# smoothieboard-alt-p6.net
KiCad netlist of a schematic drawn in Altium Designer
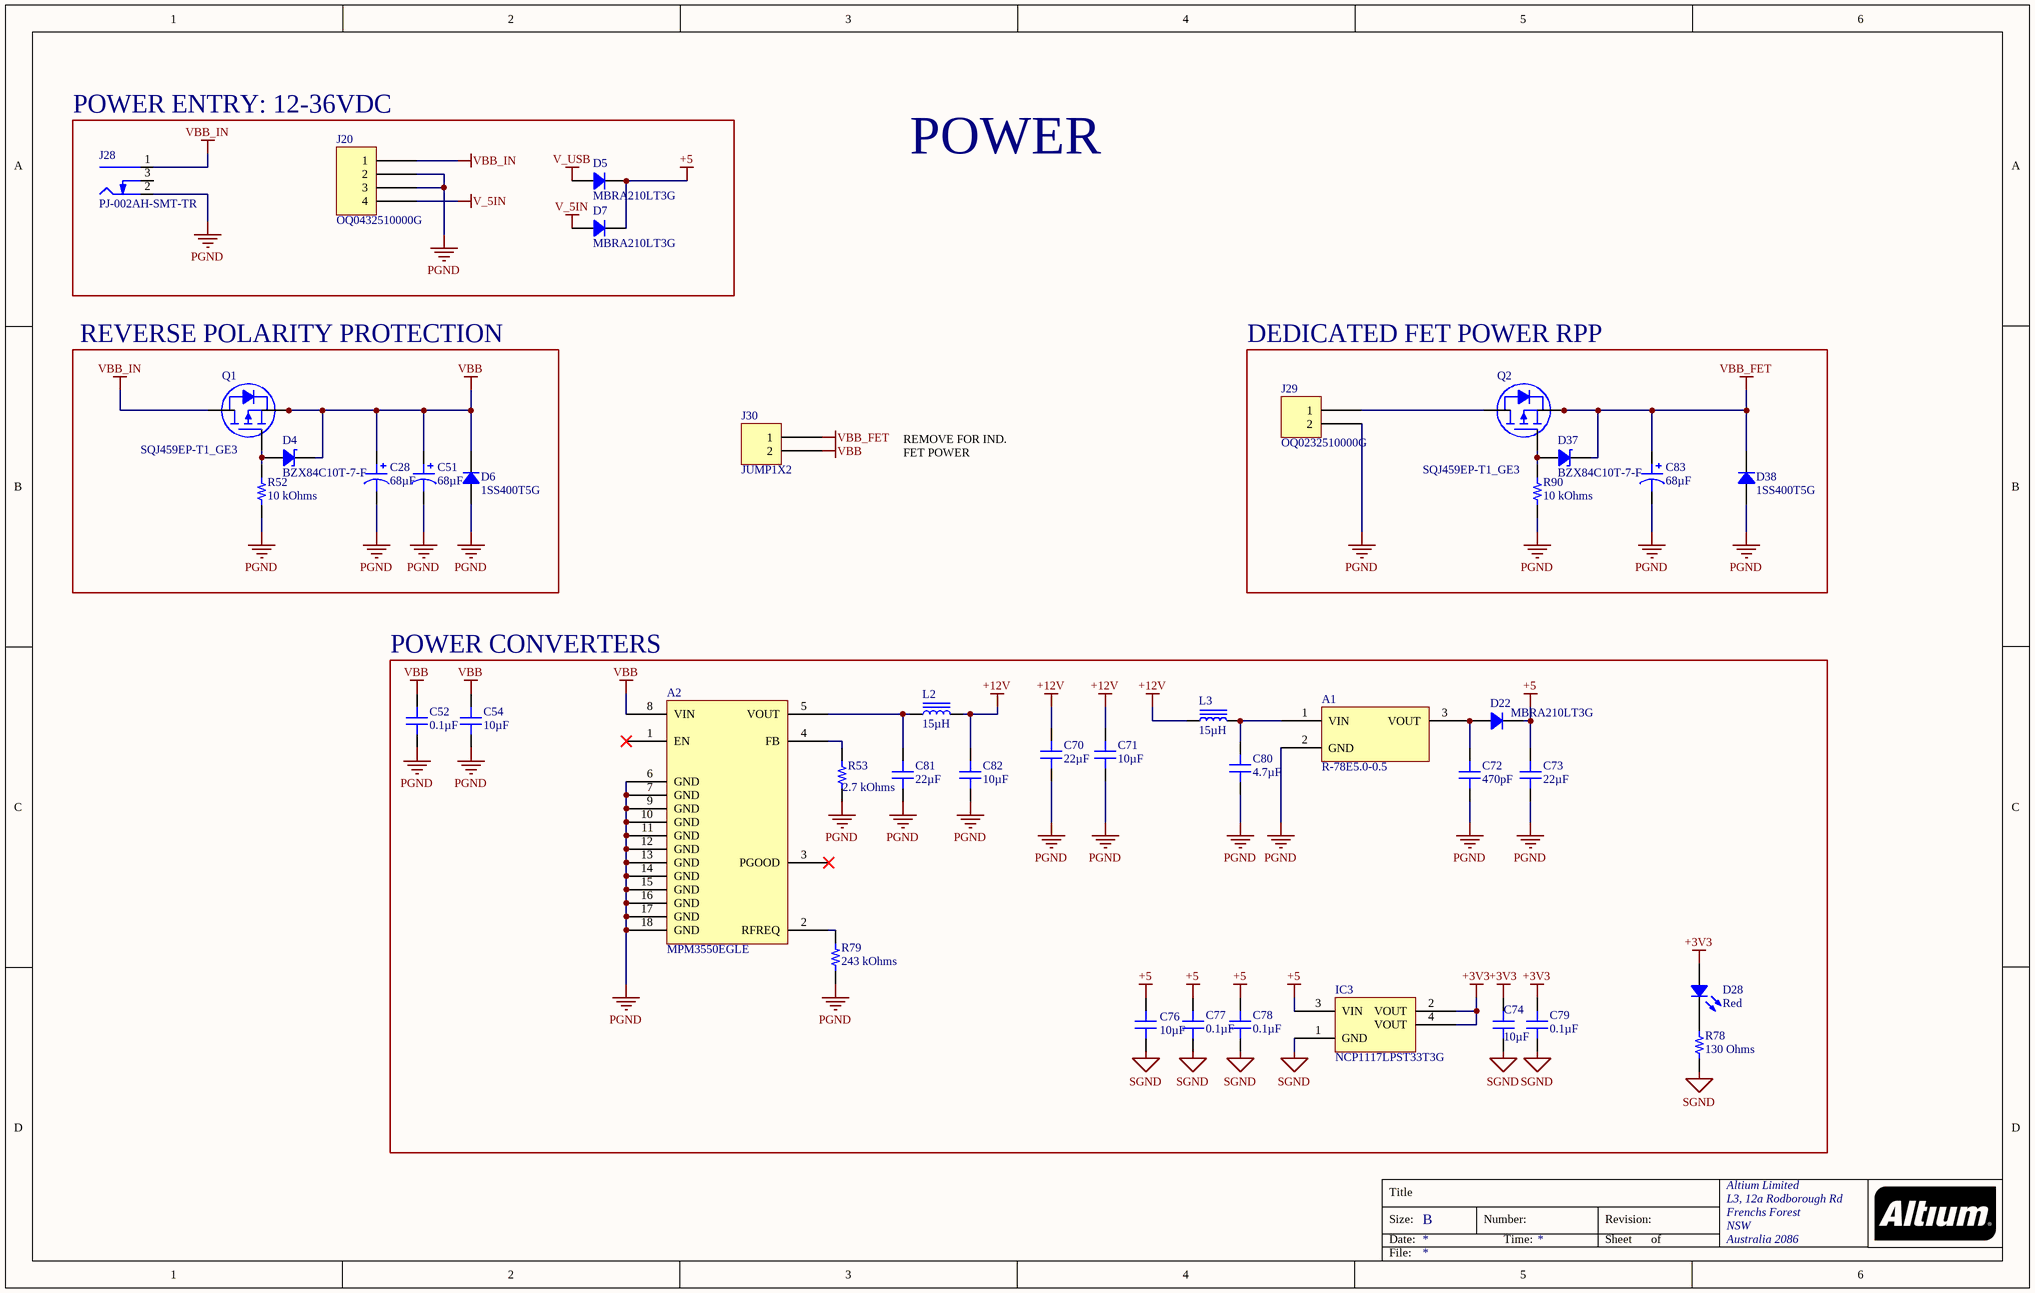
[diagram p0: smoothieboard-alt-p6.SchDoc]

(export (version "E")
  (design (tool "Eeschema 10.0.6"))
  (components
    (comp (ref "A1")
      (value "R-78E5.0-0.5")
      (footprint "RECOM POWER R-78E3.3-1.0")
      (description "DC DC CONVERTER 5V 3W")
      (fields (field (name "MANUFACTURER") "Recom Power"))
      (libsource (lib "CAL") (part "RECOM R-78E"))
    )
    (comp (ref "A2")
      (value "MPM3550EGLE")
      (footprint "MPS LGA-18 12x12x4.2mm")
      (description "DC/DC POWER MODULE 5A 1.0 TO 12.")
      (fields (field (name "MANUFACTURER") "Monolithic Power Systems Inc."))
      (libsource (lib "CAL") (part "MPS MPM3550E"))
    )
    (comp (ref "C28")
      (value "68µF")
      (footprint "CAP ALSMD 8.3MM H10.5MM")
      (description "CAP ALUM 68UF 20% 63V SMD")
      (fields
        (field (name "PART NUMBER") "EEE-FK1J680UP")
        (field (name "MANUFACTURER") "Panasonic Electronic Components")
      )
      (libsource (lib "CAL") (part "Polarised Capacitor"))
    )
    (comp (ref "C51")
      (value "68µF")
      (footprint "CAP ALSMD 8.3MM H10.5MM")
      (description "CAP ALUM 68UF 20% 63V SMD")
      (fields
        (field (name "PART NUMBER") "EEE-FK1J680UP")
        (field (name "MANUFACTURER") "Panasonic Electronic Components")
      )
      (libsource (lib "CAL") (part "Polarised Capacitor"))
    )
    (comp (ref "C52")
      (value "0.1µF")
      (footprint "CAP 0805_2012")
      (description "CAP CER 0.1UF 50V X7R 0805")
      (fields (field (name "PART NUMBER") "0805J0500104JXT") (field (name "MANUFACTURER") "Knowles Syfer"))
      (libsource (lib "CAL") (part "Capacitor"))
    )
    (comp (ref "C54")
      (value "10µF")
      (footprint "CAP 0805_2012")
      (description "0805 (2012MM) X5R (EIA) 50VDC 10")
      (fields
        (field (name "PART NUMBER") "GRM21BR61H106KE43L")
        (field (name "MANUFACTURER") "Murata Electronics")
      )
      (libsource (lib "CAL") (part "Capacitor"))
    )
    (comp (ref "C70")
      (value "22µF")
      (footprint "CAP 0805_2012")
      (description "CAP CER 22UF 16V X5R 0805")
      (fields
        (field (name "PART NUMBER") "CL21A226MOCLRNC")
        (field (name "MANUFACTURER") "Samsung Electro-Mechanics")
      )
      (libsource (lib "CAL") (part "Capacitor"))
    )
    (comp (ref "C71")
      (value "10µF")
      (footprint "CAP 0805_2012")
      (description "0805 (2012MM) X5R (EIA) 50VDC 10")
      (fields
        (field (name "PART NUMBER") "GRM21BR61H106KE43L")
        (field (name "MANUFACTURER") "Murata Electronics")
      )
      (libsource (lib "CAL") (part "Capacitor"))
    )
    (comp (ref "C72")
      (value "470pF")
      (footprint "CAP 0805_2012")
      (description "CAP CER 470PF 16V X7R 0805")
      (fields (field (name "PART NUMBER") "885012207031") (field (name "MANUFACTURER") "Würth Elektronik"))
      (libsource (lib "CAL") (part "Capacitor"))
    )
    (comp (ref "C73")
      (value "22µF")
      (footprint "CAP 0805_2012")
      (description "CAP CER 22UF 16V X5R 0805")
      (fields
        (field (name "PART NUMBER") "CL21A226MOCLRNC")
        (field (name "MANUFACTURER") "Samsung Electro-Mechanics")
      )
      (libsource (lib "CAL") (part "Capacitor"))
    )
    (comp (ref "C74")
      (value "10µF")
      (footprint "CAP 0603_1608")
      (description "CAP CER 10UF 6.3V X5R 0603")
      (fields
        (field (name "PART NUMBER") "GRM188R60J106KE47D")
        (field (name "MANUFACTURER") "Murata Electronics")
      )
      (libsource (lib "CAL") (part "Capacitor"))
    )
    (comp (ref "C76")
      (value "10µF")
      (footprint "CAP 0603_1608")
      (description "CAP CER 10UF 6.3V X5R 0603")
      (fields
        (field (name "PART NUMBER") "GRM188R60J106KE47D")
        (field (name "MANUFACTURER") "Murata Electronics")
      )
      (libsource (lib "CAL") (part "Capacitor"))
    )
    (comp (ref "C77")
      (value "0.1µF")
      (footprint "CAP 0402_1005")
      (description "CAP CER 0.1UF 6.3V X5R 0402")
      (fields (field (name "PART NUMBER") "CC0402MRX5R5BB104") (field (name "MANUFACTURER") "Yageo"))
      (libsource (lib "CAL") (part "Capacitor"))
    )
    (comp (ref "C78")
      (value "0.1µF")
      (footprint "CAP 0402_1005")
      (description "CAP CER 0.1UF 6.3V X5R 0402")
      (fields (field (name "PART NUMBER") "CC0402MRX5R5BB104") (field (name "MANUFACTURER") "Yageo"))
      (libsource (lib "CAL") (part "Capacitor"))
    )
    (comp (ref "C79")
      (value "0.1µF")
      (footprint "CAP 0402_1005")
      (description "CAP CER 0.1UF 6.3V X5R 0402")
      (fields (field (name "PART NUMBER") "CC0402MRX5R5BB104") (field (name "MANUFACTURER") "Yageo"))
      (libsource (lib "CAL") (part "Capacitor"))
    )
    (comp (ref "C80")
      (value "4.7µF")
      (footprint "CAP 0805_2012")
      (description "CAP CER 4.7UF 50V X7S 0805")
      (fields
        (field (name "PART NUMBER") "GRM21BC71H475KE11K")
        (field (name "MANUFACTURER") "Murata Electronics")
      )
      (libsource (lib "CAL") (part "Capacitor"))
    )
    (comp (ref "C81")
      (value "22µF")
      (footprint "CAP 0805_2012")
      (description "CAP CER 22UF 16V X5R 0805")
      (fields
        (field (name "PART NUMBER") "CL21A226MOCLRNC")
        (field (name "MANUFACTURER") "Samsung Electro-Mechanics")
      )
      (libsource (lib "CAL") (part "Capacitor"))
    )
    (comp (ref "C82")
      (value "10µF")
      (footprint "CAP 0805_2012")
      (description "0805 (2012MM) X5R (EIA) 50VDC 10")
      (fields
        (field (name "PART NUMBER") "GRM21BR61H106KE43L")
        (field (name "MANUFACTURER") "Murata Electronics")
      )
      (libsource (lib "CAL") (part "Capacitor"))
    )
    (comp (ref "C83")
      (value "68µF")
      (footprint "CAP ALSMD 8.3MM H10.5MM")
      (description "CAP ALUM 68UF 20% 63V SMD")
      (fields
        (field (name "PART NUMBER") "EEE-FK1J680UP")
        (field (name "MANUFACTURER") "Panasonic Electronic Components")
      )
      (libsource (lib "CAL") (part "Polarised Capacitor"))
    )
    (comp (ref "D4")
      (value "BZX84C10T-7-F")
      (footprint "DIODES SOT-523")
      (description "DIODE ZENER 10V 150MW SOT523")
      (fields (field (name "MANUFACTURER") "Diodes Incorporated") (field (name "TOLERANCE") "±6%"))
      (libsource (lib "CAL") (part "Diode Zener"))
    )
    (comp (ref "D5")
      (value "MBRA210LT3G")
      (footprint "DO214AC SMA")
      (description "DIODE SCHOTTKY 10V 2A SMA")
      (fields (field (name "MANUFACTURER") "ON Semiconductor"))
      (libsource (lib "CAL") (part "Diode"))
    )
    (comp (ref "D6")
      (value "1SS400T5G")
      (footprint "SOD-523")
      (description "DIODE GEN PURP 100V 200MA SOD523")
      (fields (field (name "MANUFACTURER") "ON Semiconductor"))
      (libsource (lib "CAL") (part "Diode"))
    )
    (comp (ref "D7")
      (value "MBRA210LT3G")
      (footprint "DO214AC SMA")
      (description "DIODE SCHOTTKY 10V 2A SMA")
      (fields (field (name "MANUFACTURER") "ON Semiconductor"))
      (libsource (lib "CAL") (part "Diode"))
    )
    (comp (ref "D22")
      (value "MBRA210LT3G")
      (footprint "DO214AC SMA")
      (description "DIODE SCHOTTKY 10V 2A SMA")
      (fields (field (name "MANUFACTURER") "ON Semiconductor"))
      (libsource (lib "CAL") (part "Diode"))
    )
    (comp (ref "D28")
      (value "Red")
      (footprint "LED 0603_1608 RED")
      (description "LED RED CLEAR 2SMD")
      (fields
        (field (name "PART NUMBER") "EAST16084RA0")
        (field (name "MANUFACTURER") "Everlight Electronics Co Ltd")
      )
      (libsource (lib "CAL") (part "LED"))
    )
    (comp (ref "D37")
      (value "BZX84C10T-7-F")
      (footprint "DIODES SOT-523")
      (description "DIODE ZENER 10V 150MW SOT523")
      (fields (field (name "MANUFACTURER") "Diodes Incorporated") (field (name "TOLERANCE") "±6%"))
      (libsource (lib "CAL") (part "Diode Zener"))
    )
    (comp (ref "D38")
      (value "1SS400T5G")
      (footprint "SOD-523")
      (description "DIODE GEN PURP 100V 200MA SOD523")
      (fields (field (name "MANUFACTURER") "ON Semiconductor"))
      (libsource (lib "CAL") (part "Diode"))
    )
    (comp (ref "IC3")
      (value "NCP1117LPST33T3G")
      (footprint "ON SEMI SOT-223 ST(318H)")
      (description "IC REG LINEAR 3.3V 1A SOT223")
      (fields (field (name "MANUFACTURER") "ON Semiconductor"))
      (libsource (lib "CAL") (part "ON Semi NCP1117"))
    )
    (comp (ref "J20")
      (value "OQ0432510000G")
      (footprint "FCI 06-381-4PIN")
      (description "TERM BLOCK HDR 4POS 90DEG 3.81MM")
      (fields (field (name "MANUFACTURER") "Amphenol Anytek"))
      (libsource (lib "CAL") (part "4 Pin"))
    )
    (comp (ref "J28")
      (value "PJ-002AH-SMT-TR")
      (footprint "CUI PJ-002AH-SMT-TR")
      (description "CONN PWR JACK 2X5.5MM SOLDER")
      (fields (field (name "MANUFACTURER") "CUI Devices"))
      (libsource (lib "CAL") (part "Barrel Connector"))
    )
    (comp (ref "J29")
      (value "OQ0232510000G")
      (footprint "FCI 06-381-2PIN")
      (description "TERM BLOCK HDR 2POS 90DEG 3.81MM")
      (fields (field (name "MANUFACTURER") "Amphenol Anytek"))
      (libsource (lib "CAL") (part "2 Pin"))
    )
    (comp (ref "J30")
      (value "JUMP1X2")
      (footprint "smoothie-lib:JUMP1X2")
      (libsource (lib "smoothie-lib") (part "JUMP1X2"))
    )
    (comp (ref "L2")
      (value "15µH")
      (footprint "IND 0806_2016")
      (description "FIXED IND 15UH 420MA 1.895OHM SM")
      (fields
        (field (name "PART NUMBER") "SDED20161T-150MS")
        (field (name "MANUFACTURER") "Delta Electronics/Cyntec")
      )
      (libsource (lib "CAL") (part "Inductor"))
    )
    (comp (ref "L3")
      (value "15µH")
      (footprint "IND 0806_2016")
      (description "FIXED IND 15UH 420MA 1.895OHM SM")
      (fields
        (field (name "PART NUMBER") "SDED20161T-150MS")
        (field (name "MANUFACTURER") "Delta Electronics/Cyntec")
      )
      (libsource (lib "CAL") (part "Inductor"))
    )
    (comp (ref "Q1")
      (value "SQJ459EP-T1_GE3")
      (footprint "POWER PAK SO-8")
      (libsource (lib "smoothie-lib") (part "SQJ459EP-T1_GE3"))
    )
    (comp (ref "Q2")
      (value "SQJ459EP-T1_GE3")
      (footprint "POWER PAK SO-8")
      (libsource (lib "smoothie-lib") (part "SQJ459EP-T1_GE3"))
    )
    (comp (ref "R52")
      (value "10 kOhms")
      (footprint "RES 0402_1005")
      (description "RES SMD 10K OHM 5% 1/16W 0402")
      (fields (field (name "PART NUMBER") "CRCW040210K0JNTD") (field (name "MANUFACTURER") "Vishay Dale"))
      (libsource (lib "CAL") (part "Resistor"))
    )
    (comp (ref "R53")
      (value "2.7 kOhms")
      (footprint "RES 0402_1005")
      (description "RES SMD 2.7K OHM 1% 1/5W 0402")
      (fields (field (name "PART NUMBER") "CRCW04022K70FKEDHP") (field (name "MANUFACTURER") "Vishay Dale"))
      (libsource (lib "CAL") (part "Resistor"))
    )
    (comp (ref "R78")
      (value "130 Ohms")
      (footprint "RES 0402_1005")
      (description "RES SMD 130 OHM 5% 1/5W 0402")
      (fields
        (field (name "PART NUMBER") "ERJ-PA2J131X")
        (field (name "MANUFACTURER") "Panasonic Electronic Components")
      )
      (libsource (lib "CAL") (part "Resistor"))
    )
    (comp (ref "R79")
      (value "243 kOhms")
      (footprint "RES 0402_1005")
      (description "RES SMD 243K OHM 1% 1/16W 0402")
      (fields (field (name "PART NUMBER") "CR0402-FX-2433GLF") (field (name "MANUFACTURER") "Bourns Inc."))
      (libsource (lib "CAL") (part "Resistor"))
    )
    (comp (ref "R90")
      (value "10 kOhms")
      (footprint "RES 0402_1005")
      (description "RES SMD 10K OHM 5% 1/16W 0402")
      (fields (field (name "PART NUMBER") "CRCW040210K0JNTD") (field (name "MANUFACTURER") "Vishay Dale"))
      (libsource (lib "CAL") (part "Resistor"))
    )
  )
  (nets
    (net (code "1") (name "+3V3") (class "Default")
      (node (ref "C74") (pin "2") (pinfunction "2_2") (pintype "passive"))
      (node (ref "C79") (pin "2") (pinfunction "2_2") (pintype "passive"))
      (node (ref "D28") (pin "1") (pinfunction "1_1") (pintype "passive"))
      (node (ref "IC3") (pin "2") (pinfunction "VOUT_2") (pintype "passive"))
      (node (ref "IC3") (pin "4") (pinfunction "VOUT_4") (pintype "passive"))
    )
    (net (code "2") (name "+5") (class "Default")
      (node (ref "C73") (pin "2") (pinfunction "2_2") (pintype "passive"))
      (node (ref "C76") (pin "2") (pinfunction "2_2") (pintype "passive"))
      (node (ref "C77") (pin "2") (pinfunction "2_2") (pintype "passive"))
      (node (ref "C78") (pin "2") (pinfunction "2_2") (pintype "passive"))
      (node (ref "D22") (pin "2") (pinfunction "2_2") (pintype "passive"))
      (node (ref "D5") (pin "2") (pinfunction "2_2") (pintype "passive"))
      (node (ref "D7") (pin "2") (pinfunction "2_2") (pintype "passive"))
      (node (ref "IC3") (pin "3") (pinfunction "VIN_3") (pintype "passive"))
    )
    (net (code "3") (name "+12V") (class "Default")
      (node (ref "C70") (pin "2") (pinfunction "2_2") (pintype "passive"))
      (node (ref "C71") (pin "2") (pinfunction "2_2") (pintype "passive"))
      (node (ref "C82") (pin "2") (pinfunction "2_2") (pintype "passive"))
      (node (ref "L2") (pin "2") (pinfunction "2_2") (pintype "passive"))
      (node (ref "L3") (pin "1") (pinfunction "1_1") (pintype "passive"))
    )
    (net (code "4") (name "Net-(A1-VIN)") (class "Default")
      (node (ref "A1") (pin "1") (pinfunction "VIN_1") (pintype "passive"))
      (node (ref "C80") (pin "2") (pinfunction "2_2") (pintype "passive"))
      (node (ref "L3") (pin "2") (pinfunction "2_2") (pintype "passive"))
    )
    (net (code "5") (name "Net-(A1-VOUT)") (class "Default")
      (node (ref "A1") (pin "3") (pinfunction "VOUT_3") (pintype "passive"))
      (node (ref "C72") (pin "2") (pinfunction "2_2") (pintype "passive"))
      (node (ref "D22") (pin "1") (pinfunction "1_1") (pintype "passive"))
    )
    (net (code "6") (name "Net-(A2-FB)") (class "Default")
      (node (ref "A2") (pin "4") (pinfunction "FB_4") (pintype "passive"))
      (node (ref "R53") (pin "2") (pinfunction "2_2") (pintype "passive"))
    )
    (net (code "7") (name "Net-(A2-RFREQ)") (class "Default")
      (node (ref "A2") (pin "2") (pinfunction "RFREQ_2") (pintype "passive"))
      (node (ref "R79") (pin "2") (pinfunction "2_2") (pintype "passive"))
    )
    (net (code "8") (name "Net-(A2-VOUT)") (class "Default")
      (node (ref "A2") (pin "5") (pinfunction "VOUT_5") (pintype "passive"))
      (node (ref "C81") (pin "2") (pinfunction "2_2") (pintype "passive"))
      (node (ref "L2") (pin "1") (pinfunction "1_1") (pintype "passive"))
    )
    (net (code "9") (name "Net-(D28-Pad2)") (class "Default")
      (node (ref "D28") (pin "2") (pinfunction "2_2") (pintype "passive"))
      (node (ref "R78") (pin "2") (pinfunction "2_2") (pintype "passive"))
    )
    (net (code "10") (name "Net-(Q1-G)") (class "Default")
      (node (ref "D4") (pin "1") (pinfunction "1_1") (pintype "passive"))
      (node (ref "Q1") (pin "4") (pinfunction "G_4") (pintype "passive"))
      (node (ref "R52") (pin "2") (pinfunction "2_2") (pintype "passive"))
    )
    (net (code "11") (name "Net-(Q2-D)") (class "Default")
      (node (ref "J29") (pin "1") (pinfunction "1_1") (pintype "passive"))
      (node (ref "Q2") (pin "5") (pinfunction "D_5") (pintype "passive"))
    )
    (net (code "12") (name "Net-(Q2-G)") (class "Default")
      (node (ref "D37") (pin "1") (pinfunction "1_1") (pintype "passive"))
      (node (ref "Q2") (pin "4") (pinfunction "G_4") (pintype "passive"))
      (node (ref "R90") (pin "2") (pinfunction "2_2") (pintype "passive"))
    )
    (net (code "13") (name "PGND") (class "Default")
      (node (ref "A1") (pin "2") (pinfunction "GND_2") (pintype "passive"))
      (node (ref "A2") (pin "10") (pinfunction "GND_10") (pintype "passive"))
      (node (ref "A2") (pin "11") (pinfunction "GND_11") (pintype "passive"))
      (node (ref "A2") (pin "12") (pinfunction "GND_12") (pintype "passive"))
      (node (ref "A2") (pin "13") (pinfunction "GND_13") (pintype "passive"))
      (node (ref "A2") (pin "14") (pinfunction "GND_14") (pintype "passive"))
      (node (ref "A2") (pin "15") (pinfunction "GND_15") (pintype "passive"))
      (node (ref "A2") (pin "16") (pinfunction "GND_16") (pintype "passive"))
      (node (ref "A2") (pin "17") (pinfunction "GND_17") (pintype "passive"))
      (node (ref "A2") (pin "18") (pinfunction "GND_18") (pintype "passive"))
      (node (ref "A2") (pin "6") (pinfunction "GND_6") (pintype "passive"))
      (node (ref "A2") (pin "7") (pinfunction "GND_7") (pintype "passive"))
      (node (ref "A2") (pin "9") (pinfunction "GND_9") (pintype "passive"))
      (node (ref "C28") (pin "2") (pinfunction "2_2") (pintype "passive"))
      (node (ref "C51") (pin "2") (pinfunction "2_2") (pintype "passive"))
      (node (ref "C52") (pin "1") (pinfunction "1_1") (pintype "passive"))
      (node (ref "C54") (pin "1") (pinfunction "1_1") (pintype "passive"))
      (node (ref "C70") (pin "1") (pinfunction "1_1") (pintype "passive"))
      (node (ref "C71") (pin "1") (pinfunction "1_1") (pintype "passive"))
      (node (ref "C72") (pin "1") (pinfunction "1_1") (pintype "passive"))
      (node (ref "C73") (pin "1") (pinfunction "1_1") (pintype "passive"))
      (node (ref "C80") (pin "1") (pinfunction "1_1") (pintype "passive"))
      (node (ref "C81") (pin "1") (pinfunction "1_1") (pintype "passive"))
      (node (ref "C82") (pin "1") (pinfunction "1_1") (pintype "passive"))
      (node (ref "C83") (pin "2") (pinfunction "2_2") (pintype "passive"))
      (node (ref "D38") (pin "1") (pinfunction "1_1") (pintype "passive"))
      (node (ref "D6") (pin "1") (pinfunction "1_1") (pintype "passive"))
      (node (ref "J20") (pin "2") (pinfunction "2_2") (pintype "passive"))
      (node (ref "J20") (pin "3") (pinfunction "3_3") (pintype "passive"))
      (node (ref "J28") (pin "2") (pinfunction "Outer_2") (pintype "passive"))
      (node (ref "J29") (pin "2") (pinfunction "2_2") (pintype "passive"))
      (node (ref "R52") (pin "1") (pinfunction "1_1") (pintype "passive"))
      (node (ref "R53") (pin "1") (pinfunction "1_1") (pintype "passive"))
      (node (ref "R79") (pin "1") (pinfunction "1_1") (pintype "passive"))
      (node (ref "R90") (pin "1") (pinfunction "1_1") (pintype "passive"))
    )
    (net (code "14") (name "SGND") (class "Default")
      (node (ref "C74") (pin "1") (pinfunction "1_1") (pintype "passive"))
      (node (ref "C76") (pin "1") (pinfunction "1_1") (pintype "passive"))
      (node (ref "C77") (pin "1") (pinfunction "1_1") (pintype "passive"))
      (node (ref "C78") (pin "1") (pinfunction "1_1") (pintype "passive"))
      (node (ref "C79") (pin "1") (pinfunction "1_1") (pintype "passive"))
      (node (ref "IC3") (pin "1") (pinfunction "GND_1") (pintype "passive"))
      (node (ref "R78") (pin "1") (pinfunction "1_1") (pintype "passive"))
    )
    (net (code "15") (name "VBB") (class "Default")
      (node (ref "A2") (pin "8") (pinfunction "VIN_8") (pintype "passive"))
      (node (ref "C28") (pin "1") (pinfunction "1_1") (pintype "passive"))
      (node (ref "C51") (pin "1") (pinfunction "1_1") (pintype "passive"))
      (node (ref "C52") (pin "2") (pinfunction "2_2") (pintype "passive"))
      (node (ref "C54") (pin "2") (pinfunction "2_2") (pintype "passive"))
      (node (ref "D4") (pin "2") (pinfunction "2_2") (pintype "passive"))
      (node (ref "D6") (pin "2") (pinfunction "2_2") (pintype "passive"))
      (node (ref "J30") (pin "2") (pinfunction "2_2") (pintype "passive"))
      (node (ref "Q1") (pin "1") (pinfunction "S_1") (pintype "passive"))
      (node (ref "Q1") (pin "2") (pinfunction "S_2") (pintype "passive"))
      (node (ref "Q1") (pin "3") (pinfunction "S_3") (pintype "passive"))
    )
    (net (code "16") (name "VBB_FET") (class "Default")
      (node (ref "C83") (pin "1") (pinfunction "1_1") (pintype "passive"))
      (node (ref "D37") (pin "2") (pinfunction "2_2") (pintype "passive"))
      (node (ref "D38") (pin "2") (pinfunction "2_2") (pintype "passive"))
      (node (ref "J30") (pin "1") (pinfunction "1_1") (pintype "passive"))
      (node (ref "Q2") (pin "1") (pinfunction "S_1") (pintype "passive"))
      (node (ref "Q2") (pin "2") (pinfunction "S_2") (pintype "passive"))
      (node (ref "Q2") (pin "3") (pinfunction "S_3") (pintype "passive"))
    )
    (net (code "17") (name "VBB_IN") (class "Default")
      (node (ref "J20") (pin "1") (pinfunction "1_1") (pintype "passive"))
      (node (ref "J28") (pin "1") (pinfunction "Centre_1") (pintype "passive"))
      (node (ref "Q1") (pin "5") (pinfunction "D_5") (pintype "passive"))
    )
    (net (code "18") (name "V_5IN") (class "Default")
      (node (ref "D7") (pin "1") (pinfunction "1_1") (pintype "passive"))
      (node (ref "J20") (pin "4") (pinfunction "4_4") (pintype "passive"))
    )
    (net (code "19") (name "V_USB") (class "Default")
      (node (ref "D5") (pin "1") (pinfunction "1_1") (pintype "passive"))
    )
    (net (code "20") (name "unconnected-(A2-EN-Pad1)") (class "Default")
      (node (ref "A2") (pin "1") (pinfunction "EN_1") (pintype "passive+no_connect"))
    )
    (net (code "21") (name "unconnected-(A2-PGOOD-Pad3)") (class "Default")
      (node (ref "A2") (pin "3") (pinfunction "PGOOD_3") (pintype "passive+no_connect"))
    )
    (net (code "22") (name "unconnected-(J28-SW-Pad3)") (class "Default")
      (node (ref "J28") (pin "3") (pinfunction "SW_3") (pintype "passive"))
    )
  )
)
